# W404C.net
KiCad netlist of a schematic drawn in EAGLE
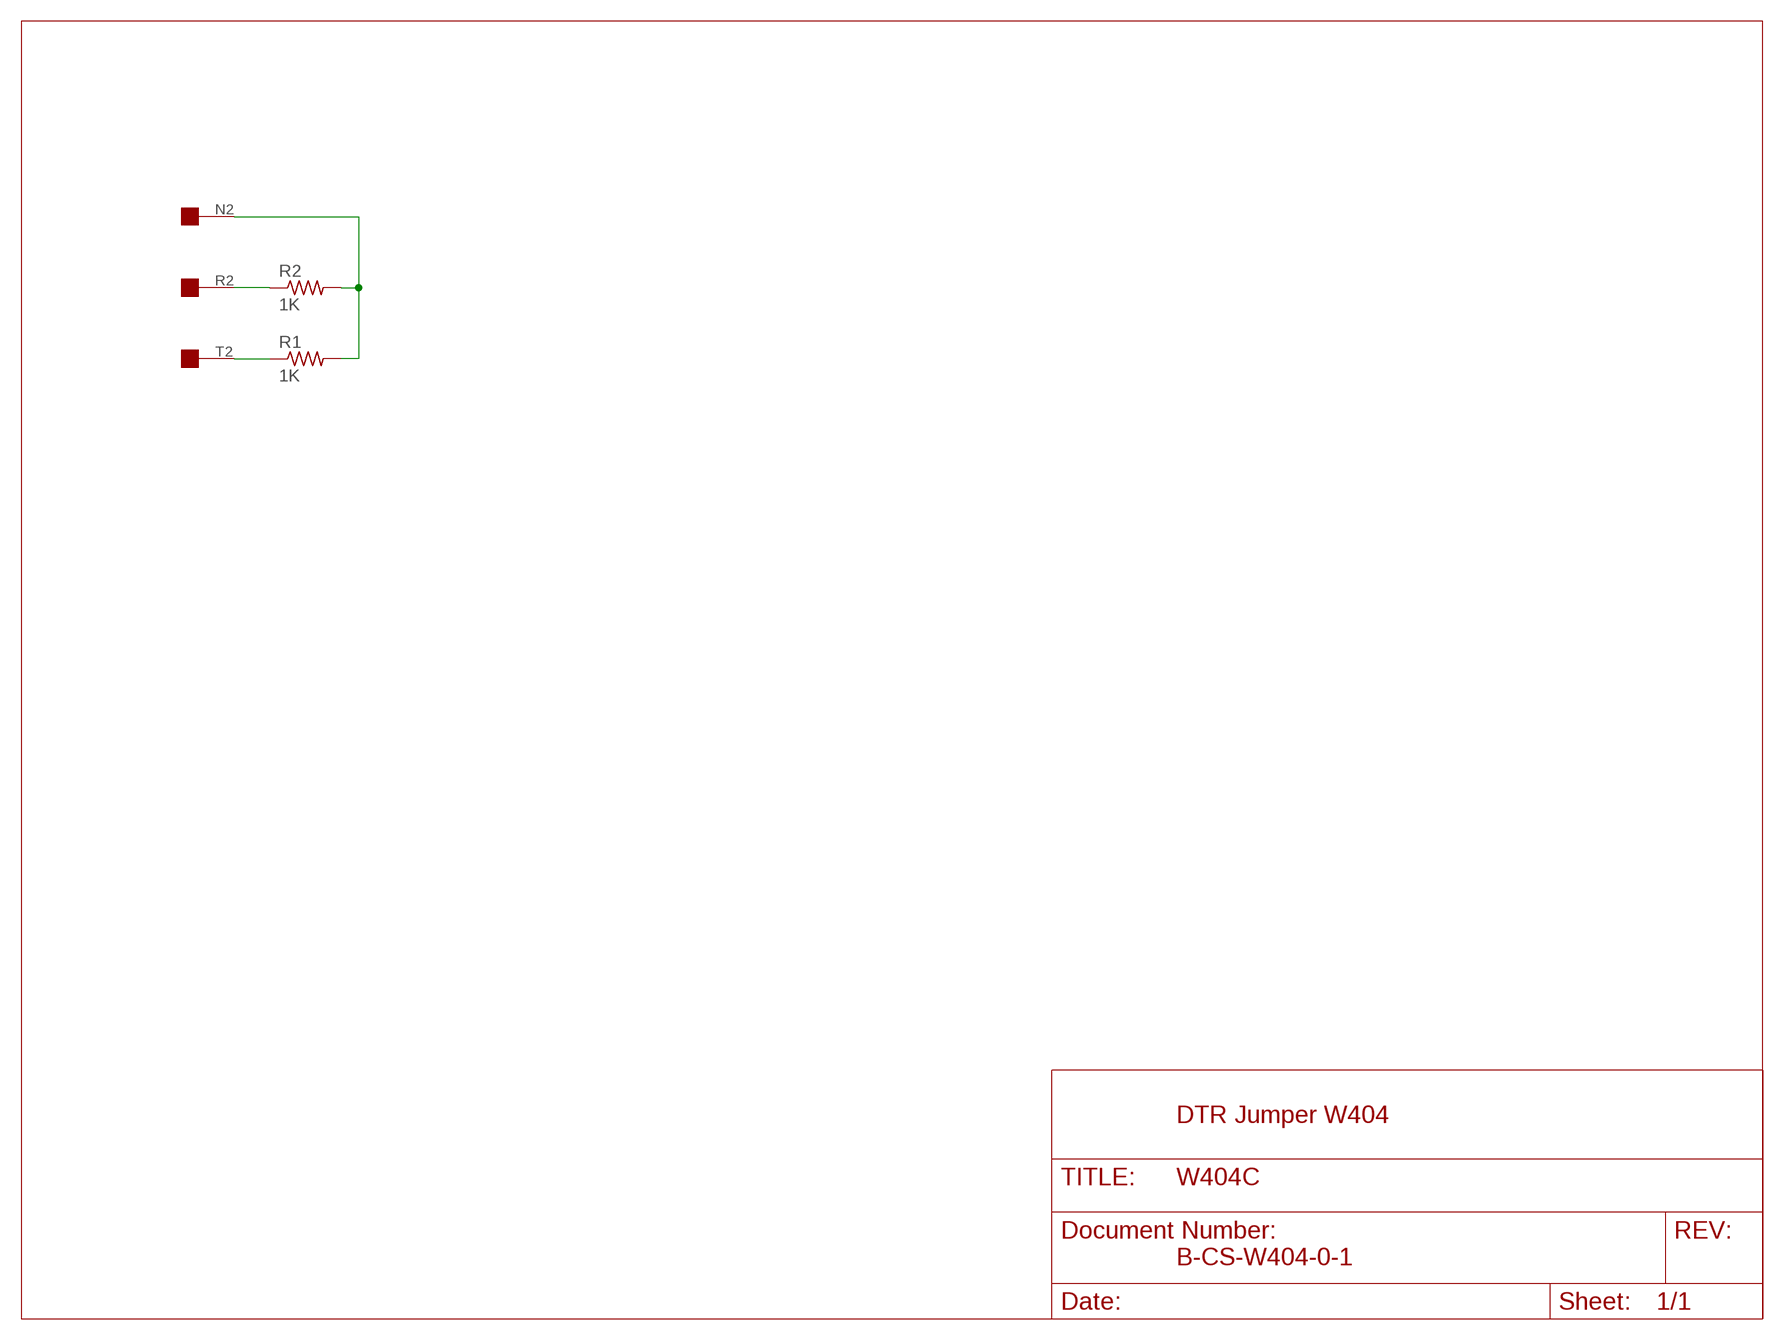
[diagram p0: schematic, sheet 1]

(export (version "E")
  (design (tool "Eeschema 10.0.6"))
  (components
    (comp (ref "R1")
      (value "1K")
      (footprint "eagle-import:0818_25")
      (libsource (lib "eagle-import") (part "R-US_0818/25"))
    )
    (comp (ref "R2")
      (value "1K")
      (footprint "eagle-import:0818_25")
      (libsource (lib "eagle-import") (part "R-US_0818/25"))
    )
    (comp (ref "U$2")
      (value "EDGE-1")
      (footprint "eagle-import:EDGE-CON1")
      (libsource (lib "eagle-import") (part "EDGE-1"))
    )
  )
  (nets
    (net (code "1") (name "Net-(U$2L-1)") (class "Default")
      (node (ref "R1") (pin "2") (pinfunction "2_2") (pintype "passive"))
      (node (ref "R2") (pin "2") (pinfunction "2_2") (pintype "passive"))
      (node (ref "U$2") (pin "N2") (pinfunction "1_N2") (pintype "bidirectional"))
    )
    (net (code "2") (name "Net-(U$2N-1)") (class "Default")
      (node (ref "R2") (pin "1") (pinfunction "1_1") (pintype "passive"))
      (node (ref "U$2") (pin "R2") (pinfunction "1_R2") (pintype "bidirectional"))
    )
    (net (code "3") (name "Net-(U$2P-1)") (class "Default")
      (node (ref "R1") (pin "1") (pinfunction "1_1") (pintype "passive"))
      (node (ref "U$2") (pin "T2") (pinfunction "1_T2") (pintype "bidirectional"))
    )
  )
)
